# fire_alarm.net
KiCad netlist of a schematic drawn in EAGLE
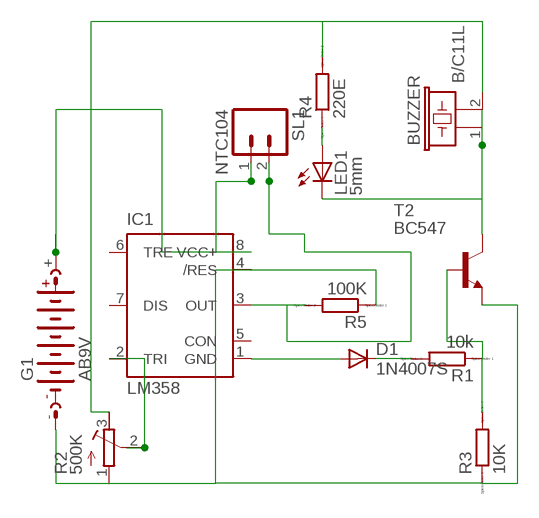
[diagram p0: schematic, sheet 1]

(export (version "E")
  (design (tool "Eeschema 10.0.6"))
  (components
    (comp (ref "BUZZER")
      (value "B/C11L")
      (footprint "eagle-import:B_C11L")
      (libsource (lib "eagle-import") (part "B/C11L"))
    )
    (comp (ref "D1")
      (value "1N4007S")
      (footprint "eagle-import:DO35-10")
      (libsource (lib "eagle-import") (part "1N4148DO35-10"))
    )
    (comp (ref "G1")
      (value "AB9V")
      (footprint "eagle-import:AB9V")
      (libsource (lib "eagle-import") (part "AB9V"))
    )
    (comp (ref "IC1")
      (value "LM358")
      (footprint "eagle-import:DIL-08")
      (fields (field (name "MF") "Arrow Electronics") (field (name "MPN") "NE555N"))
      (libsource (lib "eagle-import") (part "NE555"))
    )
    (comp (ref "LED1")
      (value "5mm")
      (footprint "eagle-import:LED5MM")
      (libsource (lib "eagle-import") (part "LED5MM"))
    )
    (comp (ref "R1")
      (value "10k")
      (footprint "eagle-import:0204_7")
      (libsource (lib "eagle-import") (part "R0204/7"))
    )
    (comp (ref "R2")
      (value "500K")
      (footprint "eagle-import:RTRIM64P")
      (libsource (lib "eagle-import") (part "R-TRIMM64P"))
    )
    (comp (ref "R3")
      (value "10K")
      (footprint "eagle-import:0204_7")
      (libsource (lib "eagle-import") (part "R0204/7"))
    )
    (comp (ref "R4")
      (value "220E")
      (footprint "eagle-import:0204_7")
      (libsource (lib "eagle-import") (part "R0204/7"))
    )
    (comp (ref "R5")
      (value "100K")
      (footprint "eagle-import:0204_7")
      (libsource (lib "eagle-import") (part "R0204/7"))
    )
    (comp (ref "SL1")
      (value "NTC104")
      (footprint "eagle-import:02P")
      (libsource (lib "eagle-import") (part "M02"))
    )
    (comp (ref "T2")
      (value "BC547")
      (footprint "eagle-import:TO92")
      (libsource (lib "eagle-import") (part "BC547"))
    )
  )
  (nets
    (net (code "1") (name "Net-(D1-PadC)") (class "Default")
      (node (ref "D1") (pin "C") (pinfunction "C_C") (pintype "passive"))
      (node (ref "R1") (pin "2") (pinfunction "2_2") (pintype "passive"))
    )
    (net (code "2") (name "Net-(IC1-GND)") (class "Default")
      (node (ref "D1") (pin "A") (pinfunction "A_A") (pintype "passive"))
      (node (ref "IC1") (pin "1") (pinfunction "GND_1") (pintype "power_in"))
    )
    (net (code "3") (name "Net-(IC1-OUT)") (class "Default")
      (node (ref "IC1") (pin "3") (pinfunction "OUT_3") (pintype "output"))
      (node (ref "R5") (pin "2") (pinfunction "2_2") (pintype "passive"))
      (node (ref "SL1") (pin "2") (pinfunction "2_2") (pintype "passive"))
    )
    (net (code "4") (name "Net-(IC1-TRI)") (class "Default")
      (node (ref "IC1") (pin "2") (pinfunction "TRI_2") (pintype "input"))
      (node (ref "R2") (pin "2") (pinfunction "S_2") (pintype "passive"))
    )
    (net (code "5") (name "Net-(IC1-VCC+)") (class "Default")
      (node (ref "BUZZER") (pin "2") (pinfunction "2_2") (pintype "passive"))
      (node (ref "G1") (pin "+") (pinfunction "+_+") (pintype "passive"))
      (node (ref "IC1") (pin "8") (pinfunction "VCC+_8") (pintype "power_in"))
      (node (ref "R2") (pin "3") (pinfunction "A_3") (pintype "passive"))
      (node (ref "R4") (pin "2") (pinfunction "2_2") (pintype "passive"))
      (node (ref "SL1") (pin "1") (pinfunction "1_1") (pintype "passive"))
    )
    (net (code "6") (name "Net-(IC1-{slash}RES)") (class "Default")
      (node (ref "G1") (pin "-") (pinfunction "-_-") (pintype "passive"))
      (node (ref "IC1") (pin "4") (pinfunction "/RES_4") (pintype "input"))
      (node (ref "R2") (pin "1") (pinfunction "E_1") (pintype "passive"))
      (node (ref "R3") (pin "1") (pinfunction "1_1") (pintype "passive"))
      (node (ref "R5") (pin "1") (pinfunction "1_1") (pintype "passive"))
      (node (ref "T2") (pin "1") (pinfunction "E_1") (pintype "passive"))
    )
    (net (code "7") (name "Net-(LED1-C)") (class "Default")
      (node (ref "BUZZER") (pin "1") (pinfunction "1_1") (pintype "passive"))
      (node (ref "LED1") (pin "K") (pinfunction "C_K") (pintype "passive"))
      (node (ref "T2") (pin "3") (pinfunction "C_3") (pintype "passive"))
    )
    (net (code "8") (name "Net-(LED1-PadA)") (class "Default")
      (node (ref "LED1") (pin "A") (pinfunction "A_A") (pintype "passive"))
      (node (ref "R4") (pin "1") (pinfunction "1_1") (pintype "passive"))
    )
    (net (code "9") (name "Net-(T2-B)") (class "Default")
      (node (ref "R1") (pin "1") (pinfunction "1_1") (pintype "passive"))
      (node (ref "R3") (pin "2") (pinfunction "2_2") (pintype "passive"))
      (node (ref "T2") (pin "2") (pinfunction "B_2") (pintype "passive"))
    )
    (net (code "10") (name "unconnected-(IC1-CON-Pad5)") (class "Default")
      (node (ref "IC1") (pin "5") (pinfunction "CON_5") (pintype "input"))
    )
    (net (code "11") (name "unconnected-(IC1-DIS-Pad7)") (class "Default")
      (node (ref "IC1") (pin "7") (pinfunction "DIS_7") (pintype "input"))
    )
    (net (code "12") (name "unconnected-(IC1-TRE-Pad6)") (class "Default")
      (node (ref "IC1") (pin "6") (pinfunction "TRE_6") (pintype "input"))
    )
  )
)
